# IO_PWR_FMU_REV_1A.net
KiCad netlist of a schematic drawn in Altium Designer
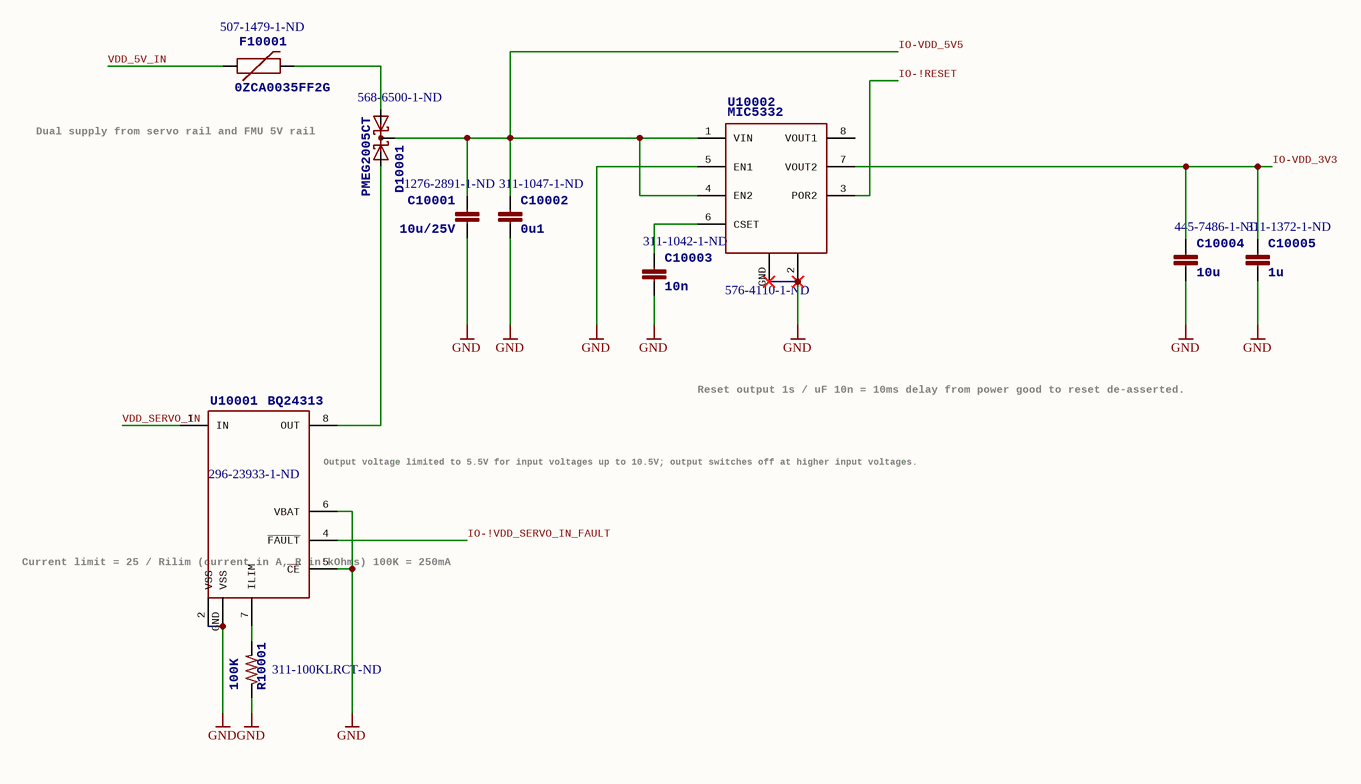
[diagram p0: IO_PWR_FMU_REV_1A.SchDoc]

(export (version "E")
  (design (tool "Eeschema 10.0.6"))
  (components
    (comp (ref "C10001")
      (value "10u/25V")
      (footprint "0805-CAP")
      (description "CAP CER 10UF 25V 10% X5R 0805")
      (fields
        (field (name "PARTNO") "CL21A106KAYNNNE")
        (field (name "SUPPLIER PART NUMBER 1") "1276-2891-1-ND")
        (field (name "3DR_PARTNO") "ECM0714")
      )
      (libsource (lib "pixhawk2") (part "CAP0805"))
    )
    (comp (ref "C10002")
      (value "0u1")
      (footprint "0402-CAP")
      (description "CAP CER 0.1UF 16V Y5V 0402")
      (fields
        (field (name "PARTNO") "CC0402ZRY5V7BB104")
        (field (name "SUPPLIER PART NUMBER 1") "311-1047-1-ND")
        (field (name "3DR_PARTNO") "ECM0700")
      )
      (libsource (lib "pixhawk2") (part "CAP0402"))
    )
    (comp (ref "C10003")
      (value "10n")
      (footprint "0402-CAP")
      (description "CAP CER 10000PF 16V 10% X7R 0402")
      (fields
        (field (name "PARTNO") "CC0402KRX7R7BB103")
        (field (name "SUPPLIER PART NUMBER 1") "311-1042-1-ND")
        (field (name "3DR_PARTNO") "ECM0711")
      )
      (libsource (lib "pixhawk2") (part "CAP0402"))
    )
    (comp (ref "C10004")
      (value "10u")
      (footprint "0603-CAP")
      (description "CAP CER 10UF 10V 10% X5R 0603")
      (fields
        (field (name "PARTNO") "C1608X5R1A106K080AC")
        (field (name "SUPPLIER PART NUMBER 1") "445-7486-1-ND")
        (field (name "3DR_PARTNO") "ECM0712")
      )
      (libsource (lib "pixhawk2") (part "CAP0603"))
    )
    (comp (ref "C10005")
      (value "1u")
      (footprint "0603-CAP")
      (description "CAP CER 1UF 16V Y5V 0603")
      (fields
        (field (name "PARTNO") "CC0603ZRY5V7BB105")
        (field (name "SUPPLIER PART NUMBER 1") "311-1372-1-ND")
        (field (name "3DR_PARTNO") "ECM0705")
      )
      (libsource (lib "pixhawk2") (part "CAP0603"))
    )
    (comp (ref "D10001")
      (value "PMEG2005CT")
      (footprint "SOT23-3")
      (description "DIODE SCHOTTKY 20V 500MA TO236AB")
      (fields (field (name "SUPPLIER PART NUMBER 1") "568-6500-1-ND") (field (name "3DR_PARTNO") "ECM0838"))
      (libsource (lib "pixhawk2") (part "PMEG2005CT"))
    )
    (comp (ref "F10001")
      (value "0ZCA0035FF2G")
      (footprint "PTC-1206")
      (description "PTC RESTTBLE 0.35A 16V CHIP 1206")
      (fields (field (name "SUPPLIER PART NUMBER 1") "507-1479-1-ND") (field (name "3DR_PARTNO") "ECM0802"))
      (libsource (lib "pixhawk2") (part "PTCSMD"))
    )
    (comp (ref "Logo")
      (value "ProfiCNC_LOGO")
      (footprint "ProfiCNC_medium")
      (libsource (lib "ProfiCNC") (part "ProfiCNC_LOGO"))
    )
    (comp (ref "R10001")
      (value "100K")
      (footprint "0402-RES")
      (description "RES 100K OHM 1/16W 1% 0402 SMD")
      (fields
        (field (name "SUPPLIER PART NUMBER 1") "311-100KLRCT-ND")
        (field (name "3DR_PARTNO") "ECM0818")
        (field (name "PARTNO") "RC0402FR-07100KL")
      )
      (libsource (lib "pixhawk2") (part "RESISTOR0402-RES"))
    )
    (comp (ref "U10001")
      (value "BQ24313")
      (footprint "QFN8-DSG")
      (description "IC LI+ CHARGER FRONT END 8-SON")
      (fields
        (field (name "SUPPLIER PART NUMBER 1") "296-23933-1-ND")
        (field (name "3DR_PARTNO") "ECM0824")
        (field (name "PARTNO") "BQ24313DSGT")
      )
      (libsource (lib "pixhawk2") (part "BQ24313"))
    )
    (comp (ref "U10002")
      (value "MIC5332")
      (footprint "MLF-8-EPAD")
      (description "IC REG LDO 3.3V 0.3A 8TMLF")
      (fields
        (field (name "SUPPLIER PART NUMBER 1") "576-4110-1-ND")
        (field (name "3DR_PARTNO") "ECM0832")
        (field (name "PARTNO") "MIC5332-SSYMT TR")
      )
      (libsource (lib "pixhawk2") (part "MIC5332"))
    )
  )
  (nets
    (net (code "1") (name "/IO-!RESET") (class "Default")
      (node (ref "U10002") (pin "3") (pinfunction "POR2_3") (pintype "passive"))
    )
    (net (code "2") (name "/IO-!VDD_SERVO_IN_FAULT") (class "Default")
      (node (ref "U10001") (pin "4") (pinfunction "~{FAULT}_4") (pintype "passive"))
    )
    (net (code "3") (name "/IO-VDD_3V3") (class "Default")
      (node (ref "C10004") (pin "P$1") (pinfunction "1_P$1") (pintype "passive"))
      (node (ref "C10005") (pin "P$1") (pinfunction "1_P$1") (pintype "passive"))
      (node (ref "U10002") (pin "7") (pinfunction "VOUT2_7") (pintype "passive"))
    )
    (net (code "4") (name "/IO-VDD_5V5") (class "Default")
      (node (ref "C10001") (pin "P$1") (pinfunction "1_P$1") (pintype "passive"))
      (node (ref "C10002") (pin "P$1") (pinfunction "1_P$1") (pintype "passive"))
      (node (ref "D10001") (pin "3") (pinfunction "CC_3") (pintype "passive"))
      (node (ref "U10002") (pin "1") (pinfunction "VIN_1") (pintype "passive"))
      (node (ref "U10002") (pin "4") (pinfunction "EN2_4") (pintype "passive"))
    )
    (net (code "5") (name "/VDD_5V_IN") (class "Default")
      (node (ref "F10001") (pin "1") (pinfunction "1_1") (pintype "passive"))
    )
    (net (code "6") (name "/VDD_SERVO_IN") (class "Default")
      (node (ref "U10001") (pin "1") (pinfunction "IN_1") (pintype "passive"))
    )
    (net (code "7") (name "GND") (class "Default")
      (node (ref "C10001") (pin "P$2") (pinfunction "2_P$2") (pintype "passive"))
      (node (ref "C10002") (pin "P$2") (pinfunction "2_P$2") (pintype "passive"))
      (node (ref "C10003") (pin "P$2") (pinfunction "2_P$2") (pintype "passive"))
      (node (ref "C10004") (pin "P$2") (pinfunction "2_P$2") (pintype "passive"))
      (node (ref "C10005") (pin "P$2") (pinfunction "2_P$2") (pintype "passive"))
      (node (ref "R10001") (pin "P$1") (pinfunction "1_P$1") (pintype "passive"))
      (node (ref "U10001") (pin "2") (pinfunction "VSS_2") (pintype "passive"))
      (node (ref "U10001") (pin "5") (pinfunction "~{CE}_5") (pintype "passive"))
      (node (ref "U10001") (pin "6") (pinfunction "VBAT_6") (pintype "passive"))
      (node (ref "U10001") (pin "GND") (pinfunction "VSS_GND") (pintype "passive"))
      (node (ref "U10002") (pin "2") (pinfunction "GND_2") (pintype "power_in"))
      (node (ref "U10002") (pin "5") (pinfunction "EN1_5") (pintype "passive"))
      (node (ref "U10002") (pin "GND") (pinfunction "GND_GND") (pintype "power_in"))
    )
    (net (code "8") (name "Net-(C10003-1)") (class "Default")
      (node (ref "C10003") (pin "P$1") (pinfunction "1_P$1") (pintype "passive"))
      (node (ref "U10002") (pin "6") (pinfunction "CSET_6") (pintype "passive"))
    )
    (net (code "9") (name "Net-(D10001-A1)") (class "Default")
      (node (ref "D10001") (pin "1") (pinfunction "A1_1") (pintype "passive"))
      (node (ref "F10001") (pin "2") (pinfunction "2_2") (pintype "passive"))
    )
    (net (code "10") (name "Net-(D10001-A2)") (class "Default")
      (node (ref "D10001") (pin "2") (pinfunction "A2_2") (pintype "passive"))
      (node (ref "U10001") (pin "8") (pinfunction "OUT_8") (pintype "passive"))
    )
    (net (code "11") (name "Net-(R10001-2)") (class "Default")
      (node (ref "R10001") (pin "P$2") (pinfunction "2_P$2") (pintype "passive"))
      (node (ref "U10001") (pin "7") (pinfunction "ILIM_7") (pintype "passive"))
    )
    (net (code "12") (name "unconnected-(U10002-VOUT1-Pad8)") (class "Default")
      (node (ref "U10002") (pin "8") (pinfunction "VOUT1_8") (pintype "passive"))
    )
  )
)
